# Thermocouples.net
KiCad netlist of a schematic drawn in Altium Designer
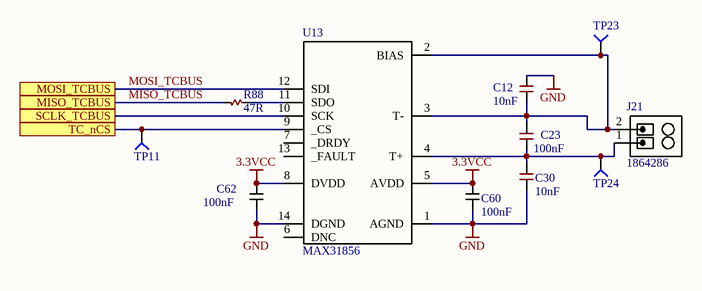
[diagram p0: Thermocouples.SchDoc]

(export (version "E")
  (design (tool "Eeschema 10.0.6"))
  (components
    (comp (ref "C12")
      (value "10nF")
      (footprint "C0402")
      (description "CAP CER 10nF 50V X7R 0402")
      (fields (field (name "TOLERANCE") "5%") (field (name "MANUFACTURER") "Murata"))
      (libsource (lib "Capacitors") (part "10nF 0402 50V X7R"))
    )
    (comp (ref "C23")
      (value "100nF")
      (footprint "C0603")
      (description "CAP CER 0603 100nF 50V 10% X7R")
      (fields (field (name "MANUFACTURER") "Kemet") (field (name "PART") "100nF 50V X7R 0603"))
      (libsource (lib "Capacitors") (part "100nF 0603 50V X7R"))
    )
    (comp (ref "C30")
      (value "10nF")
      (footprint "C0402")
      (description "CAP CER 10nF 50V X7R 0402")
      (fields (field (name "TOLERANCE") "5%") (field (name "MANUFACTURER") "Murata"))
      (libsource (lib "Capacitors") (part "10nF 0402 50V X7R"))
    )
    (comp (ref "C60")
      (value "100nF")
      (footprint "C0201 Large Pads")
      (description "CAP CER 0.1UF 6.3V 10% X5R 0201")
      (fields (field (name "MANUFACTURER") "Samsung") (field (name "TOLERANCE") "10%"))
      (libsource (lib "Capacitors") (part "100nF 6.3V X5R 0201"))
    )
    (comp (ref "C62")
      (value "100nF")
      (footprint "C0201 Large Pads")
      (description "CAP CER 0.1UF 6.3V 10% X5R 0201")
      (fields (field (name "MANUFACTURER") "Samsung") (field (name "TOLERANCE") "10%"))
      (libsource (lib "Capacitors") (part "100nF 6.3V X5R 0201"))
    )
    (comp (ref "J21")
      (value "1864286")
      (footprint "1864286")
      (description "TERM BLOCK 2POS 45DEG 3.5MM PCB")
      (fields (field (name "MANUFACTURER") "Phoenix Contact") (field (name "TOLERANCE") "-NA-"))
      (libsource (lib "Connectors") (part "2POS 45DEG 3.5MM Push-Spring Terminal Block"))
    )
    (comp (ref "R88")
      (value "47R")
      (footprint "R0402")
      (description "RES 47 OHM 1% 1/16W 0402")
      (fields (field (name "MANUFACTURER") "Vishay Dale") (field (name "TOLERANCE") "+/- 1%"))
      (libsource (lib "Resistors") (part "47R 1% 0402"))
    )
    (comp (ref "TP11")
      (value "TP4")
      (footprint "TP-2")
      (description "Socket")
      (libsource (lib "Archim") (part "Socket"))
    )
    (comp (ref "TP23")
      (value "TP4")
      (footprint "TP-2")
      (description "Socket")
      (libsource (lib "Archim") (part "Socket"))
    )
    (comp (ref "TP24")
      (value "TP4")
      (footprint "TP-2")
      (description "Socket")
      (libsource (lib "Archim") (part "Socket"))
    )
    (comp (ref "U13")
      (value "MAX31856")
      (footprint "TSSOP-14L 65P640X110")
      (description "IC CONV THERMOCOUPLE 14TSSOP")
      (fields (field (name "MANUFACTURER") "Maxim") (field (name "VOLTAGE") "3.3V"))
      (libsource (lib "ICs-Analog") (part "MAX31856"))
    )
  )
  (nets
    (net (code "1") (name "/MISO_TCBUS") (class "Default")
      (node (ref "R88") (pin "2") (pinfunction "2_2") (pintype "passive"))
    )
    (net (code "2") (name "/MOSI_TCBUS") (class "Default")
      (node (ref "U13") (pin "12") (pinfunction "SDI_12") (pintype "power_in"))
    )
    (net (code "3") (name "/SCLK_TCBUS") (class "Default")
      (node (ref "U13") (pin "10") (pinfunction "SCK_10") (pintype "power_in"))
    )
    (net (code "4") (name "/TC_nCS") (class "Default")
      (node (ref "TP11") (pin "1") (pinfunction "1_1") (pintype "passive"))
      (node (ref "U13") (pin "9") (pinfunction "_CS_9") (pintype "power_in"))
    )
    (net (code "5") (name "3.3VCC") (class "Default")
      (node (ref "C60") (pin "2") (pinfunction "2_2") (pintype "passive"))
      (node (ref "C62") (pin "2") (pinfunction "2_2") (pintype "passive"))
      (node (ref "U13") (pin "5") (pinfunction "AVDD_5") (pintype "passive"))
      (node (ref "U13") (pin "8") (pinfunction "DVDD_8") (pintype "passive"))
    )
    (net (code "6") (name "GND") (class "Default")
      (node (ref "C12") (pin "2") (pinfunction "2_2") (pintype "passive"))
      (node (ref "C30") (pin "1") (pinfunction "1_1") (pintype "passive"))
      (node (ref "C60") (pin "1") (pinfunction "1_1") (pintype "passive"))
      (node (ref "C62") (pin "1") (pinfunction "1_1") (pintype "passive"))
      (node (ref "U13") (pin "1") (pinfunction "AGND_1") (pintype "passive"))
      (node (ref "U13") (pin "14") (pinfunction "DGND_14") (pintype "power_in"))
    )
    (net (code "7") (name "Net-(U13-BIAS)") (class "Default")
      (node (ref "C12") (pin "1") (pinfunction "1_1") (pintype "passive"))
      (node (ref "C23") (pin "2") (pinfunction "2_2") (pintype "passive"))
      (node (ref "J21") (pin "2") (pinfunction "S_2") (pintype "passive"))
      (node (ref "TP23") (pin "1") (pinfunction "1_1") (pintype "passive"))
      (node (ref "U13") (pin "2") (pinfunction "BIAS_2") (pintype "passive"))
      (node (ref "U13") (pin "3") (pinfunction "T-_3") (pintype "passive"))
    )
    (net (code "8") (name "Net-(U13-SDO)") (class "Default")
      (node (ref "R88") (pin "1") (pinfunction "1_1") (pintype "passive"))
      (node (ref "U13") (pin "11") (pinfunction "SDO_11") (pintype "power_in"))
    )
    (net (code "9") (name "Net-(U13-T+)") (class "Default")
      (node (ref "C23") (pin "1") (pinfunction "1_1") (pintype "passive"))
      (node (ref "C30") (pin "2") (pinfunction "2_2") (pintype "passive"))
      (node (ref "J21") (pin "1") (pinfunction "S_1") (pintype "passive"))
      (node (ref "TP24") (pin "1") (pinfunction "1_1") (pintype "passive"))
      (node (ref "U13") (pin "4") (pinfunction "T+_4") (pintype "passive"))
    )
    (net (code "10") (name "unconnected-(U13-DNC-Pad6)") (class "Default")
      (node (ref "U13") (pin "6") (pinfunction "DNC_6") (pintype "passive"))
    )
    (net (code "11") (name "unconnected-(U13-_DRDY-Pad7)") (class "Default")
      (node (ref "U13") (pin "7") (pinfunction "_DRDY_7") (pintype "passive"))
    )
    (net (code "12") (name "unconnected-(U13-_FAULT-Pad13)") (class "Default")
      (node (ref "U13") (pin "13") (pinfunction "_FAULT_13") (pintype "power_in"))
    )
  )
)
